# Skaarhoj_BI8-2x4v1_1.net
KiCad netlist of a schematic drawn in EAGLE
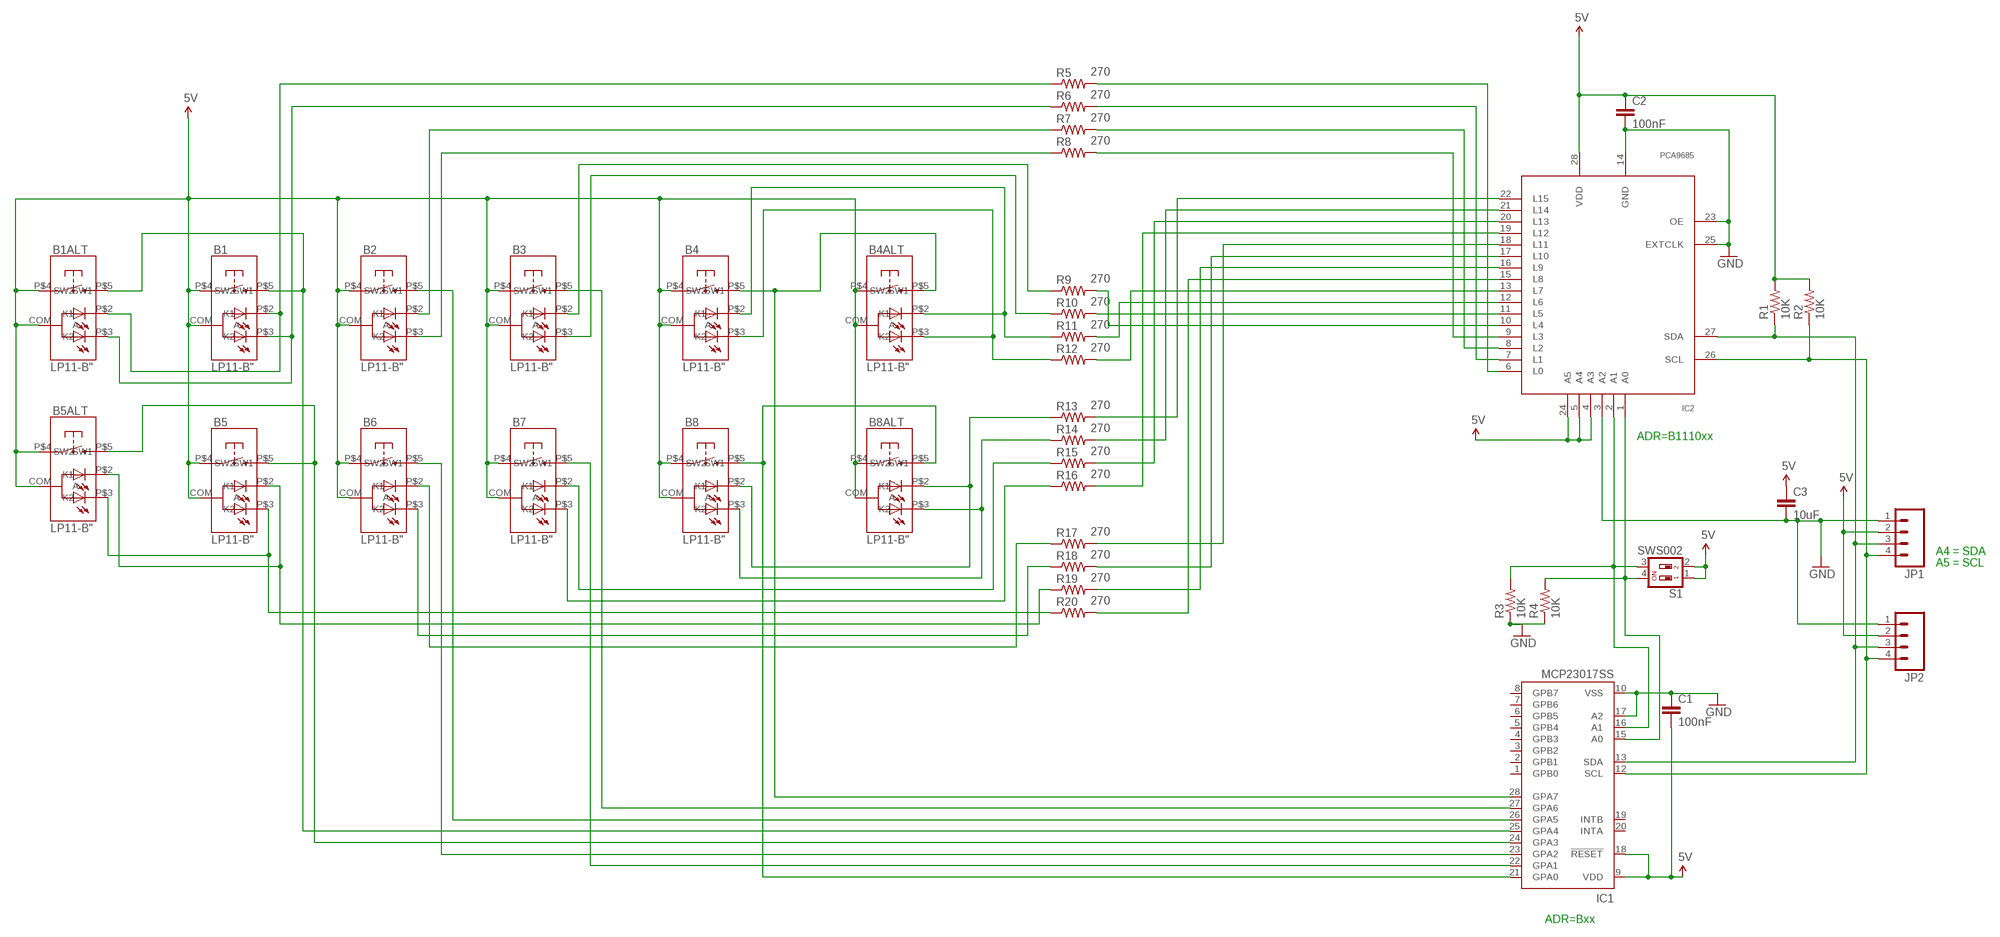
[diagram p0: schematic, sheet 1]

(export (version "E")
  (design (tool "Eeschema 10.0.6"))
  (components
    (comp (ref "B1")
      (value "LP11-B\"")
      (footprint "eagle-import:LP11")
      (libsource (lib "eagle-import") (part "LP11-B{dblquote}"))
    )
    (comp (ref "B1ALT")
      (value "LP11-B\"")
      (footprint "eagle-import:LP11")
      (libsource (lib "eagle-import") (part "LP11-B{dblquote}"))
    )
    (comp (ref "B2")
      (value "LP11-B\"")
      (footprint "eagle-import:LP11")
      (libsource (lib "eagle-import") (part "LP11-B{dblquote}"))
    )
    (comp (ref "B3")
      (value "LP11-B\"")
      (footprint "eagle-import:LP11")
      (libsource (lib "eagle-import") (part "LP11-B{dblquote}"))
    )
    (comp (ref "B4")
      (value "LP11-B\"")
      (footprint "eagle-import:LP11")
      (libsource (lib "eagle-import") (part "LP11-B{dblquote}"))
    )
    (comp (ref "B4ALT")
      (value "LP11-B\"")
      (footprint "eagle-import:LP11")
      (libsource (lib "eagle-import") (part "LP11-B{dblquote}"))
    )
    (comp (ref "B5")
      (value "LP11-B\"")
      (footprint "eagle-import:LP11")
      (libsource (lib "eagle-import") (part "LP11-B{dblquote}"))
    )
    (comp (ref "B5ALT")
      (value "LP11-B\"")
      (footprint "eagle-import:LP11")
      (libsource (lib "eagle-import") (part "LP11-B{dblquote}"))
    )
    (comp (ref "B6")
      (value "LP11-B\"")
      (footprint "eagle-import:LP11")
      (libsource (lib "eagle-import") (part "LP11-B{dblquote}"))
    )
    (comp (ref "B7")
      (value "LP11-B\"")
      (footprint "eagle-import:LP11")
      (libsource (lib "eagle-import") (part "LP11-B{dblquote}"))
    )
    (comp (ref "B8")
      (value "LP11-B\"")
      (footprint "eagle-import:LP11")
      (libsource (lib "eagle-import") (part "LP11-B{dblquote}"))
    )
    (comp (ref "B8ALT")
      (value "LP11-B\"")
      (footprint "eagle-import:LP11")
      (libsource (lib "eagle-import") (part "LP11-B{dblquote}"))
    )
    (comp (ref "C1")
      (value "100nF")
      (footprint "eagle-import:0603-CAP")
      (libsource (lib "eagle-import") (part "CAP0603-CAP"))
    )
    (comp (ref "C2")
      (value "100nF")
      (footprint "eagle-import:0603-CAP")
      (libsource (lib "eagle-import") (part "CAP0603-CAP"))
    )
    (comp (ref "C3")
      (value "10uF")
      (footprint "eagle-import:0805")
      (libsource (lib "eagle-import") (part "CAP0805"))
    )
    (comp (ref "IC1")
      (value "MCP23017SS")
      (footprint "eagle-import:SSOP28")
      (fields
        (field (name "MF") "MICROCHIP")
        (field (name "MPN") "MCP23017-E/SS")
        (field (name "MPN_1") "MCP23017-E/SS")
        (field (name "OC_FARNELL") "1467674")
        (field (name "OC_NEWARK") "31K2960")
      )
      (libsource (lib "eagle-import") (part "MCP23017SS"))
    )
    (comp (ref "IC2")
      (value "PCA9685")
      (footprint "eagle-import:TSSOP28")
      (libsource (lib "eagle-import") (part "PCA9685"))
    )
    (comp (ref "JP1")
      (value "M04PTH")
      (footprint "eagle-import:1X04")
      (libsource (lib "eagle-import") (part "M04PTH"))
    )
    (comp (ref "JP2")
      (value "M04PTH")
      (footprint "eagle-import:1X04")
      (libsource (lib "eagle-import") (part "M04PTH"))
    )
    (comp (ref "R1")
      (value "10K")
      (footprint "eagle-import:0603-RES")
      (libsource (lib "eagle-import") (part "RESISTOR0603-RES"))
    )
    (comp (ref "R2")
      (value "10K")
      (footprint "eagle-import:0603-RES")
      (libsource (lib "eagle-import") (part "RESISTOR0603-RES"))
    )
    (comp (ref "R3")
      (value "10K")
      (footprint "eagle-import:0603-RES")
      (libsource (lib "eagle-import") (part "RESISTOR0603-RES"))
    )
    (comp (ref "R4")
      (value "10K")
      (footprint "eagle-import:0603-RES")
      (libsource (lib "eagle-import") (part "RESISTOR0603-RES"))
    )
    (comp (ref "R5")
      (value "270")
      (footprint "eagle-import:0603-RES")
      (libsource (lib "eagle-import") (part "RESISTOR0603-RES"))
    )
    (comp (ref "R6")
      (value "270")
      (footprint "eagle-import:0603-RES")
      (libsource (lib "eagle-import") (part "RESISTOR0603-RES"))
    )
    (comp (ref "R7")
      (value "270")
      (footprint "eagle-import:0603-RES")
      (libsource (lib "eagle-import") (part "RESISTOR0603-RES"))
    )
    (comp (ref "R8")
      (value "270")
      (footprint "eagle-import:0603-RES")
      (libsource (lib "eagle-import") (part "RESISTOR0603-RES"))
    )
    (comp (ref "R9")
      (value "270")
      (footprint "eagle-import:0603-RES")
      (libsource (lib "eagle-import") (part "RESISTOR0603-RES"))
    )
    (comp (ref "R10")
      (value "270")
      (footprint "eagle-import:0603-RES")
      (libsource (lib "eagle-import") (part "RESISTOR0603-RES"))
    )
    (comp (ref "R11")
      (value "270")
      (footprint "eagle-import:0603-RES")
      (libsource (lib "eagle-import") (part "RESISTOR0603-RES"))
    )
    (comp (ref "R12")
      (value "270")
      (footprint "eagle-import:0603-RES")
      (libsource (lib "eagle-import") (part "RESISTOR0603-RES"))
    )
    (comp (ref "R13")
      (value "270")
      (footprint "eagle-import:0603-RES")
      (libsource (lib "eagle-import") (part "RESISTOR0603-RES"))
    )
    (comp (ref "R14")
      (value "270")
      (footprint "eagle-import:0603-RES")
      (libsource (lib "eagle-import") (part "RESISTOR0603-RES"))
    )
    (comp (ref "R15")
      (value "270")
      (footprint "eagle-import:0603-RES")
      (libsource (lib "eagle-import") (part "RESISTOR0603-RES"))
    )
    (comp (ref "R16")
      (value "270")
      (footprint "eagle-import:0603-RES")
      (libsource (lib "eagle-import") (part "RESISTOR0603-RES"))
    )
    (comp (ref "R17")
      (value "270")
      (footprint "eagle-import:0603-RES")
      (libsource (lib "eagle-import") (part "RESISTOR0603-RES"))
    )
    (comp (ref "R18")
      (value "270")
      (footprint "eagle-import:0603-RES")
      (libsource (lib "eagle-import") (part "RESISTOR0603-RES"))
    )
    (comp (ref "R19")
      (value "270")
      (footprint "eagle-import:0603-RES")
      (libsource (lib "eagle-import") (part "RESISTOR0603-RES"))
    )
    (comp (ref "R20")
      (value "270")
      (footprint "eagle-import:0603-RES")
      (libsource (lib "eagle-import") (part "RESISTOR0603-RES"))
    )
    (comp (ref "S1")
      (value "SWS002")
      (footprint "eagle-import:SMS-002")
      (libsource (lib "eagle-import") (part "SWS002"))
    )
  )
  (nets
    (net (code "1") (name "5V") (class "Default")
      (node (ref "B1") (pin "COM") (pinfunction "A_COM") (pintype "bidirectional"))
      (node (ref "B1") (pin "P$4") (pinfunction "SW1_P$4") (pintype "bidirectional"))
      (node (ref "B1ALT") (pin "COM") (pinfunction "A_COM") (pintype "bidirectional"))
      (node (ref "B1ALT") (pin "P$4") (pinfunction "SW1_P$4") (pintype "bidirectional"))
      (node (ref "B2") (pin "COM") (pinfunction "A_COM") (pintype "bidirectional"))
      (node (ref "B2") (pin "P$4") (pinfunction "SW1_P$4") (pintype "bidirectional"))
      (node (ref "B3") (pin "COM") (pinfunction "A_COM") (pintype "bidirectional"))
      (node (ref "B3") (pin "P$4") (pinfunction "SW1_P$4") (pintype "bidirectional"))
      (node (ref "B4") (pin "COM") (pinfunction "A_COM") (pintype "bidirectional"))
      (node (ref "B4") (pin "P$4") (pinfunction "SW1_P$4") (pintype "bidirectional"))
      (node (ref "B4ALT") (pin "COM") (pinfunction "A_COM") (pintype "bidirectional"))
      (node (ref "B4ALT") (pin "P$4") (pinfunction "SW1_P$4") (pintype "bidirectional"))
      (node (ref "B5") (pin "COM") (pinfunction "A_COM") (pintype "bidirectional"))
      (node (ref "B5") (pin "P$4") (pinfunction "SW1_P$4") (pintype "bidirectional"))
      (node (ref "B5ALT") (pin "COM") (pinfunction "A_COM") (pintype "bidirectional"))
      (node (ref "B5ALT") (pin "P$4") (pinfunction "SW1_P$4") (pintype "bidirectional"))
      (node (ref "B6") (pin "COM") (pinfunction "A_COM") (pintype "bidirectional"))
      (node (ref "B6") (pin "P$4") (pinfunction "SW1_P$4") (pintype "bidirectional"))
      (node (ref "B7") (pin "COM") (pinfunction "A_COM") (pintype "bidirectional"))
      (node (ref "B7") (pin "P$4") (pinfunction "SW1_P$4") (pintype "bidirectional"))
      (node (ref "B8") (pin "COM") (pinfunction "A_COM") (pintype "bidirectional"))
      (node (ref "B8") (pin "P$4") (pinfunction "SW1_P$4") (pintype "bidirectional"))
      (node (ref "B8ALT") (pin "COM") (pinfunction "A_COM") (pintype "bidirectional"))
      (node (ref "B8ALT") (pin "P$4") (pinfunction "SW1_P$4") (pintype "bidirectional"))
      (node (ref "C1") (pin "2") (pinfunction "2_2") (pintype "passive"))
      (node (ref "C2") (pin "1") (pinfunction "1_1") (pintype "passive"))
      (node (ref "C3") (pin "1") (pinfunction "1_1") (pintype "passive"))
      (node (ref "IC1") (pin "18") (pinfunction "~{RESET}_18") (pintype "input"))
      (node (ref "IC1") (pin "9") (pinfunction "VDD_9") (pintype "power_in"))
      (node (ref "IC2") (pin "24") (pinfunction "A5_24") (pintype "input"))
      (node (ref "IC2") (pin "28") (pinfunction "VDD_28") (pintype "power_in"))
      (node (ref "IC2") (pin "4") (pinfunction "A3_4") (pintype "input"))
      (node (ref "IC2") (pin "5") (pinfunction "A4_5") (pintype "input"))
      (node (ref "JP1") (pin "2") (pinfunction "2_2") (pintype "passive"))
      (node (ref "JP2") (pin "2") (pinfunction "2_2") (pintype "passive"))
      (node (ref "R1") (pin "2") (pinfunction "2_2") (pintype "passive"))
      (node (ref "R2") (pin "2") (pinfunction "2_2") (pintype "passive"))
      (node (ref "S1") (pin "1") (pinfunction "1_1") (pintype "passive"))
      (node (ref "S1") (pin "2") (pinfunction "2_2") (pintype "passive"))
    )
    (net (code "2") (name "GND") (class "Default")
      (node (ref "C1") (pin "1") (pinfunction "1_1") (pintype "passive"))
      (node (ref "C2") (pin "2") (pinfunction "2_2") (pintype "passive"))
      (node (ref "C3") (pin "2") (pinfunction "2_2") (pintype "passive"))
      (node (ref "IC1") (pin "10") (pinfunction "VSS_10") (pintype "power_in"))
      (node (ref "IC1") (pin "17") (pinfunction "A2_17") (pintype "input"))
      (node (ref "IC2") (pin "14") (pinfunction "GND_14") (pintype "power_in"))
      (node (ref "IC2") (pin "23") (pinfunction "OE_23") (pintype "input"))
      (node (ref "IC2") (pin "25") (pinfunction "EXTCLK_25") (pintype "input"))
      (node (ref "IC2") (pin "3") (pinfunction "A2_3") (pintype "input"))
      (node (ref "JP1") (pin "1") (pinfunction "1_1") (pintype "passive"))
      (node (ref "JP2") (pin "1") (pinfunction "1_1") (pintype "passive"))
      (node (ref "R3") (pin "1") (pinfunction "1_1") (pintype "passive"))
      (node (ref "R4") (pin "1") (pinfunction "1_1") (pintype "passive"))
    )
    (net (code "3") (name "Net-(B1-K1)") (class "Default")
      (node (ref "B1") (pin "P$2") (pinfunction "K1_P$2") (pintype "bidirectional"))
      (node (ref "B1ALT") (pin "P$2") (pinfunction "K1_P$2") (pintype "bidirectional"))
      (node (ref "R5") (pin "1") (pinfunction "1_1") (pintype "passive"))
    )
    (net (code "4") (name "Net-(B1-K2)") (class "Default")
      (node (ref "B1") (pin "P$3") (pinfunction "K2_P$3") (pintype "bidirectional"))
      (node (ref "B1ALT") (pin "P$3") (pinfunction "K2_P$3") (pintype "bidirectional"))
      (node (ref "R6") (pin "1") (pinfunction "1_1") (pintype "passive"))
    )
    (net (code "5") (name "Net-(B1-SW2)") (class "Default")
      (node (ref "B1") (pin "P$5") (pinfunction "SW2_P$5") (pintype "bidirectional"))
      (node (ref "B1ALT") (pin "P$5") (pinfunction "SW2_P$5") (pintype "bidirectional"))
      (node (ref "IC1") (pin "25") (pinfunction "GPA4_25") (pintype "bidirectional"))
    )
    (net (code "6") (name "Net-(B2-K1)") (class "Default")
      (node (ref "B2") (pin "P$2") (pinfunction "K1_P$2") (pintype "bidirectional"))
      (node (ref "R7") (pin "1") (pinfunction "1_1") (pintype "passive"))
    )
    (net (code "7") (name "Net-(B2-K2)") (class "Default")
      (node (ref "B2") (pin "P$3") (pinfunction "K2_P$3") (pintype "bidirectional"))
      (node (ref "R8") (pin "1") (pinfunction "1_1") (pintype "passive"))
    )
    (net (code "8") (name "Net-(B2-SW2)") (class "Default")
      (node (ref "B2") (pin "P$5") (pinfunction "SW2_P$5") (pintype "bidirectional"))
      (node (ref "IC1") (pin "26") (pinfunction "GPA5_26") (pintype "bidirectional"))
    )
    (net (code "9") (name "Net-(B3-K1)") (class "Default")
      (node (ref "B3") (pin "P$2") (pinfunction "K1_P$2") (pintype "bidirectional"))
      (node (ref "R9") (pin "1") (pinfunction "1_1") (pintype "passive"))
    )
    (net (code "10") (name "Net-(B3-K2)") (class "Default")
      (node (ref "B3") (pin "P$3") (pinfunction "K2_P$3") (pintype "bidirectional"))
      (node (ref "R10") (pin "1") (pinfunction "1_1") (pintype "passive"))
    )
    (net (code "11") (name "Net-(B3-SW2)") (class "Default")
      (node (ref "B3") (pin "P$5") (pinfunction "SW2_P$5") (pintype "bidirectional"))
      (node (ref "IC1") (pin "27") (pinfunction "GPA6_27") (pintype "bidirectional"))
    )
    (net (code "12") (name "Net-(B4-K1)") (class "Default")
      (node (ref "B4") (pin "P$2") (pinfunction "K1_P$2") (pintype "bidirectional"))
      (node (ref "B4ALT") (pin "P$2") (pinfunction "K1_P$2") (pintype "bidirectional"))
      (node (ref "R11") (pin "1") (pinfunction "1_1") (pintype "passive"))
    )
    (net (code "13") (name "Net-(B4-K2)") (class "Default")
      (node (ref "B4") (pin "P$3") (pinfunction "K2_P$3") (pintype "bidirectional"))
      (node (ref "B4ALT") (pin "P$3") (pinfunction "K2_P$3") (pintype "bidirectional"))
      (node (ref "R12") (pin "1") (pinfunction "1_1") (pintype "passive"))
    )
    (net (code "14") (name "Net-(B4-SW2)") (class "Default")
      (node (ref "B4") (pin "P$5") (pinfunction "SW2_P$5") (pintype "bidirectional"))
      (node (ref "B4ALT") (pin "P$5") (pinfunction "SW2_P$5") (pintype "bidirectional"))
      (node (ref "IC1") (pin "28") (pinfunction "GPA7_28") (pintype "bidirectional"))
    )
    (net (code "15") (name "Net-(B5-K1)") (class "Default")
      (node (ref "B5") (pin "P$2") (pinfunction "K1_P$2") (pintype "bidirectional"))
      (node (ref "B5ALT") (pin "P$2") (pinfunction "K1_P$2") (pintype "bidirectional"))
      (node (ref "R19") (pin "1") (pinfunction "1_1") (pintype "passive"))
    )
    (net (code "16") (name "Net-(B5-K2)") (class "Default")
      (node (ref "B5") (pin "P$3") (pinfunction "K2_P$3") (pintype "bidirectional"))
      (node (ref "B5ALT") (pin "P$3") (pinfunction "K2_P$3") (pintype "bidirectional"))
      (node (ref "R20") (pin "1") (pinfunction "1_1") (pintype "passive"))
    )
    (net (code "17") (name "Net-(B5-SW2)") (class "Default")
      (node (ref "B5") (pin "P$5") (pinfunction "SW2_P$5") (pintype "bidirectional"))
      (node (ref "B5ALT") (pin "P$5") (pinfunction "SW2_P$5") (pintype "bidirectional"))
      (node (ref "IC1") (pin "24") (pinfunction "GPA3_24") (pintype "bidirectional"))
    )
    (net (code "18") (name "Net-(B6-K1)") (class "Default")
      (node (ref "B6") (pin "P$2") (pinfunction "K1_P$2") (pintype "bidirectional"))
      (node (ref "R17") (pin "1") (pinfunction "1_1") (pintype "passive"))
    )
    (net (code "19") (name "Net-(B6-K2)") (class "Default")
      (node (ref "B6") (pin "P$3") (pinfunction "K2_P$3") (pintype "bidirectional"))
      (node (ref "R18") (pin "1") (pinfunction "1_1") (pintype "passive"))
    )
    (net (code "20") (name "Net-(B6-SW2)") (class "Default")
      (node (ref "B6") (pin "P$5") (pinfunction "SW2_P$5") (pintype "bidirectional"))
      (node (ref "IC1") (pin "23") (pinfunction "GPA2_23") (pintype "bidirectional"))
    )
    (net (code "21") (name "Net-(B7-K1)") (class "Default")
      (node (ref "B7") (pin "P$2") (pinfunction "K1_P$2") (pintype "bidirectional"))
      (node (ref "R15") (pin "1") (pinfunction "1_1") (pintype "passive"))
    )
    (net (code "22") (name "Net-(B7-K2)") (class "Default")
      (node (ref "B7") (pin "P$3") (pinfunction "K2_P$3") (pintype "bidirectional"))
      (node (ref "R16") (pin "1") (pinfunction "1_1") (pintype "passive"))
    )
    (net (code "23") (name "Net-(B7-SW2)") (class "Default")
      (node (ref "B7") (pin "P$5") (pinfunction "SW2_P$5") (pintype "bidirectional"))
      (node (ref "IC1") (pin "22") (pinfunction "GPA1_22") (pintype "bidirectional"))
    )
    (net (code "24") (name "Net-(B8-K1)") (class "Default")
      (node (ref "B8") (pin "P$2") (pinfunction "K1_P$2") (pintype "bidirectional"))
      (node (ref "B8ALT") (pin "P$2") (pinfunction "K1_P$2") (pintype "bidirectional"))
      (node (ref "R13") (pin "1") (pinfunction "1_1") (pintype "passive"))
    )
    (net (code "25") (name "Net-(B8-K2)") (class "Default")
      (node (ref "B8") (pin "P$3") (pinfunction "K2_P$3") (pintype "bidirectional"))
      (node (ref "B8ALT") (pin "P$3") (pinfunction "K2_P$3") (pintype "bidirectional"))
      (node (ref "R14") (pin "1") (pinfunction "1_1") (pintype "passive"))
    )
    (net (code "26") (name "Net-(B8-SW2)") (class "Default")
      (node (ref "B8") (pin "P$5") (pinfunction "SW2_P$5") (pintype "bidirectional"))
      (node (ref "B8ALT") (pin "P$5") (pinfunction "SW2_P$5") (pintype "bidirectional"))
      (node (ref "IC1") (pin "21") (pinfunction "GPA0_21") (pintype "bidirectional"))
    )
    (net (code "27") (name "Net-(IC1-A0)") (class "Default")
      (node (ref "IC1") (pin "15") (pinfunction "A0_15") (pintype "input"))
      (node (ref "IC2") (pin "1") (pinfunction "A0_1") (pintype "input"))
      (node (ref "R4") (pin "2") (pinfunction "2_2") (pintype "passive"))
      (node (ref "S1") (pin "4") (pinfunction "4_4") (pintype "passive"))
    )
    (net (code "28") (name "Net-(IC1-A1)") (class "Default")
      (node (ref "IC1") (pin "16") (pinfunction "A1_16") (pintype "input"))
      (node (ref "IC2") (pin "2") (pinfunction "A1_2") (pintype "input"))
      (node (ref "R3") (pin "2") (pinfunction "2_2") (pintype "passive"))
      (node (ref "S1") (pin "3") (pinfunction "3_3") (pintype "passive"))
    )
    (net (code "29") (name "Net-(IC1-SCL)") (class "Default")
      (node (ref "IC1") (pin "12") (pinfunction "SCL_12") (pintype "input"))
      (node (ref "IC2") (pin "26") (pinfunction "SCL_26") (pintype "input"))
      (node (ref "JP1") (pin "4") (pinfunction "4_4") (pintype "passive"))
      (node (ref "JP2") (pin "4") (pinfunction "4_4") (pintype "passive"))
      (node (ref "R2") (pin "1") (pinfunction "1_1") (pintype "passive"))
    )
    (net (code "30") (name "Net-(IC1-SDA)") (class "Default")
      (node (ref "IC1") (pin "13") (pinfunction "SDA_13") (pintype "bidirectional"))
      (node (ref "IC2") (pin "27") (pinfunction "SDA_27") (pintype "input"))
      (node (ref "JP1") (pin "3") (pinfunction "3_3") (pintype "passive"))
      (node (ref "JP2") (pin "3") (pinfunction "3_3") (pintype "passive"))
      (node (ref "R1") (pin "1") (pinfunction "1_1") (pintype "passive"))
    )
    (net (code "31") (name "Net-(IC2-L0)") (class "Default")
      (node (ref "IC2") (pin "6") (pinfunction "L0_6") (pintype "output"))
      (node (ref "R5") (pin "2") (pinfunction "2_2") (pintype "passive"))
    )
    (net (code "32") (name "Net-(IC2-L1)") (class "Default")
      (node (ref "IC2") (pin "7") (pinfunction "L1_7") (pintype "output"))
      (node (ref "R6") (pin "2") (pinfunction "2_2") (pintype "passive"))
    )
    (net (code "33") (name "Net-(IC2-L2)") (class "Default")
      (node (ref "IC2") (pin "8") (pinfunction "L2_8") (pintype "output"))
      (node (ref "R7") (pin "2") (pinfunction "2_2") (pintype "passive"))
    )
    (net (code "34") (name "Net-(IC2-L3)") (class "Default")
      (node (ref "IC2") (pin "9") (pinfunction "L3_9") (pintype "output"))
      (node (ref "R8") (pin "2") (pinfunction "2_2") (pintype "passive"))
    )
    (net (code "35") (name "Net-(IC2-L4)") (class "Default")
      (node (ref "IC2") (pin "10") (pinfunction "L4_10") (pintype "output"))
      (node (ref "R9") (pin "2") (pinfunction "2_2") (pintype "passive"))
    )
    (net (code "36") (name "Net-(IC2-L5)") (class "Default")
      (node (ref "IC2") (pin "11") (pinfunction "L5_11") (pintype "output"))
      (node (ref "R10") (pin "2") (pinfunction "2_2") (pintype "passive"))
    )
    (net (code "37") (name "Net-(IC2-L6)") (class "Default")
      (node (ref "IC2") (pin "12") (pinfunction "L6_12") (pintype "output"))
      (node (ref "R11") (pin "2") (pinfunction "2_2") (pintype "passive"))
    )
    (net (code "38") (name "Net-(IC2-L7)") (class "Default")
      (node (ref "IC2") (pin "13") (pinfunction "L7_13") (pintype "output"))
      (node (ref "R12") (pin "2") (pinfunction "2_2") (pintype "passive"))
    )
    (net (code "39") (name "Net-(IC2-L8)") (class "Default")
      (node (ref "IC2") (pin "15") (pinfunction "L8_15") (pintype "output"))
      (node (ref "R20") (pin "2") (pinfunction "2_2") (pintype "passive"))
    )
    (net (code "40") (name "Net-(IC2-L9)") (class "Default")
      (node (ref "IC2") (pin "16") (pinfunction "L9_16") (pintype "output"))
      (node (ref "R19") (pin "2") (pinfunction "2_2") (pintype "passive"))
    )
    (net (code "41") (name "Net-(IC2-L10)") (class "Default")
      (node (ref "IC2") (pin "17") (pinfunction "L10_17") (pintype "output"))
      (node (ref "R18") (pin "2") (pinfunction "2_2") (pintype "passive"))
    )
    (net (code "42") (name "Net-(IC2-L11)") (class "Default")
      (node (ref "IC2") (pin "18") (pinfunction "L11_18") (pintype "output"))
      (node (ref "R17") (pin "2") (pinfunction "2_2") (pintype "passive"))
    )
    (net (code "43") (name "Net-(IC2-L12)") (class "Default")
      (node (ref "IC2") (pin "19") (pinfunction "L12_19") (pintype "output"))
      (node (ref "R16") (pin "2") (pinfunction "2_2") (pintype "passive"))
    )
    (net (code "44") (name "Net-(IC2-L13)") (class "Default")
      (node (ref "IC2") (pin "20") (pinfunction "L13_20") (pintype "output"))
      (node (ref "R15") (pin "2") (pinfunction "2_2") (pintype "passive"))
    )
    (net (code "45") (name "Net-(IC2-L14)") (class "Default")
      (node (ref "IC2") (pin "21") (pinfunction "L14_21") (pintype "output"))
      (node (ref "R14") (pin "2") (pinfunction "2_2") (pintype "passive"))
    )
    (net (code "46") (name "Net-(IC2-L15)") (class "Default")
      (node (ref "IC2") (pin "22") (pinfunction "L15_22") (pintype "output"))
      (node (ref "R13") (pin "2") (pinfunction "2_2") (pintype "passive"))
    )
    (net (code "47") (name "unconnected-(IC1-GPB0-Pad1)") (class "Default")
      (node (ref "IC1") (pin "1") (pinfunction "GPB0_1") (pintype "bidirectional"))
    )
    (net (code "48") (name "unconnected-(IC1-GPB1-Pad2)") (class "Default")
      (node (ref "IC1") (pin "2") (pinfunction "GPB1_2") (pintype "bidirectional"))
    )
    (net (code "49") (name "unconnected-(IC1-GPB2-Pad3)") (class "Default")
      (node (ref "IC1") (pin "3") (pinfunction "GPB2_3") (pintype "bidirectional"))
    )
    (net (code "50") (name "unconnected-(IC1-GPB3-Pad4)") (class "Default")
      (node (ref "IC1") (pin "4") (pinfunction "GPB3_4") (pintype "bidirectional"))
    )
    (net (code "51") (name "unconnected-(IC1-GPB4-Pad5)") (class "Default")
      (node (ref "IC1") (pin "5") (pinfunction "GPB4_5") (pintype "bidirectional"))
    )
    (net (code "52") (name "unconnected-(IC1-GPB5-Pad6)") (class "Default")
      (node (ref "IC1") (pin "6") (pinfunction "GPB5_6") (pintype "bidirectional"))
    )
    (net (code "53") (name "unconnected-(IC1-GPB6-Pad7)") (class "Default")
      (node (ref "IC1") (pin "7") (pinfunction "GPB6_7") (pintype "bidirectional"))
    )
    (net (code "54") (name "unconnected-(IC1-GPB7-Pad8)") (class "Default")
      (node (ref "IC1") (pin "8") (pinfunction "GPB7_8") (pintype "bidirectional"))
    )
    (net (code "55") (name "unconnected-(IC1-INTA-Pad20)") (class "Default")
      (node (ref "IC1") (pin "20") (pinfunction "INTA_20") (pintype "output"))
    )
    (net (code "56") (name "unconnected-(IC1-INTB-Pad19)") (class "Default")
      (node (ref "IC1") (pin "19") (pinfunction "INTB_19") (pintype "output"))
    )
  )
)
